# Brake_rev01.net
KiCad netlist of a schematic drawn in EAGLE
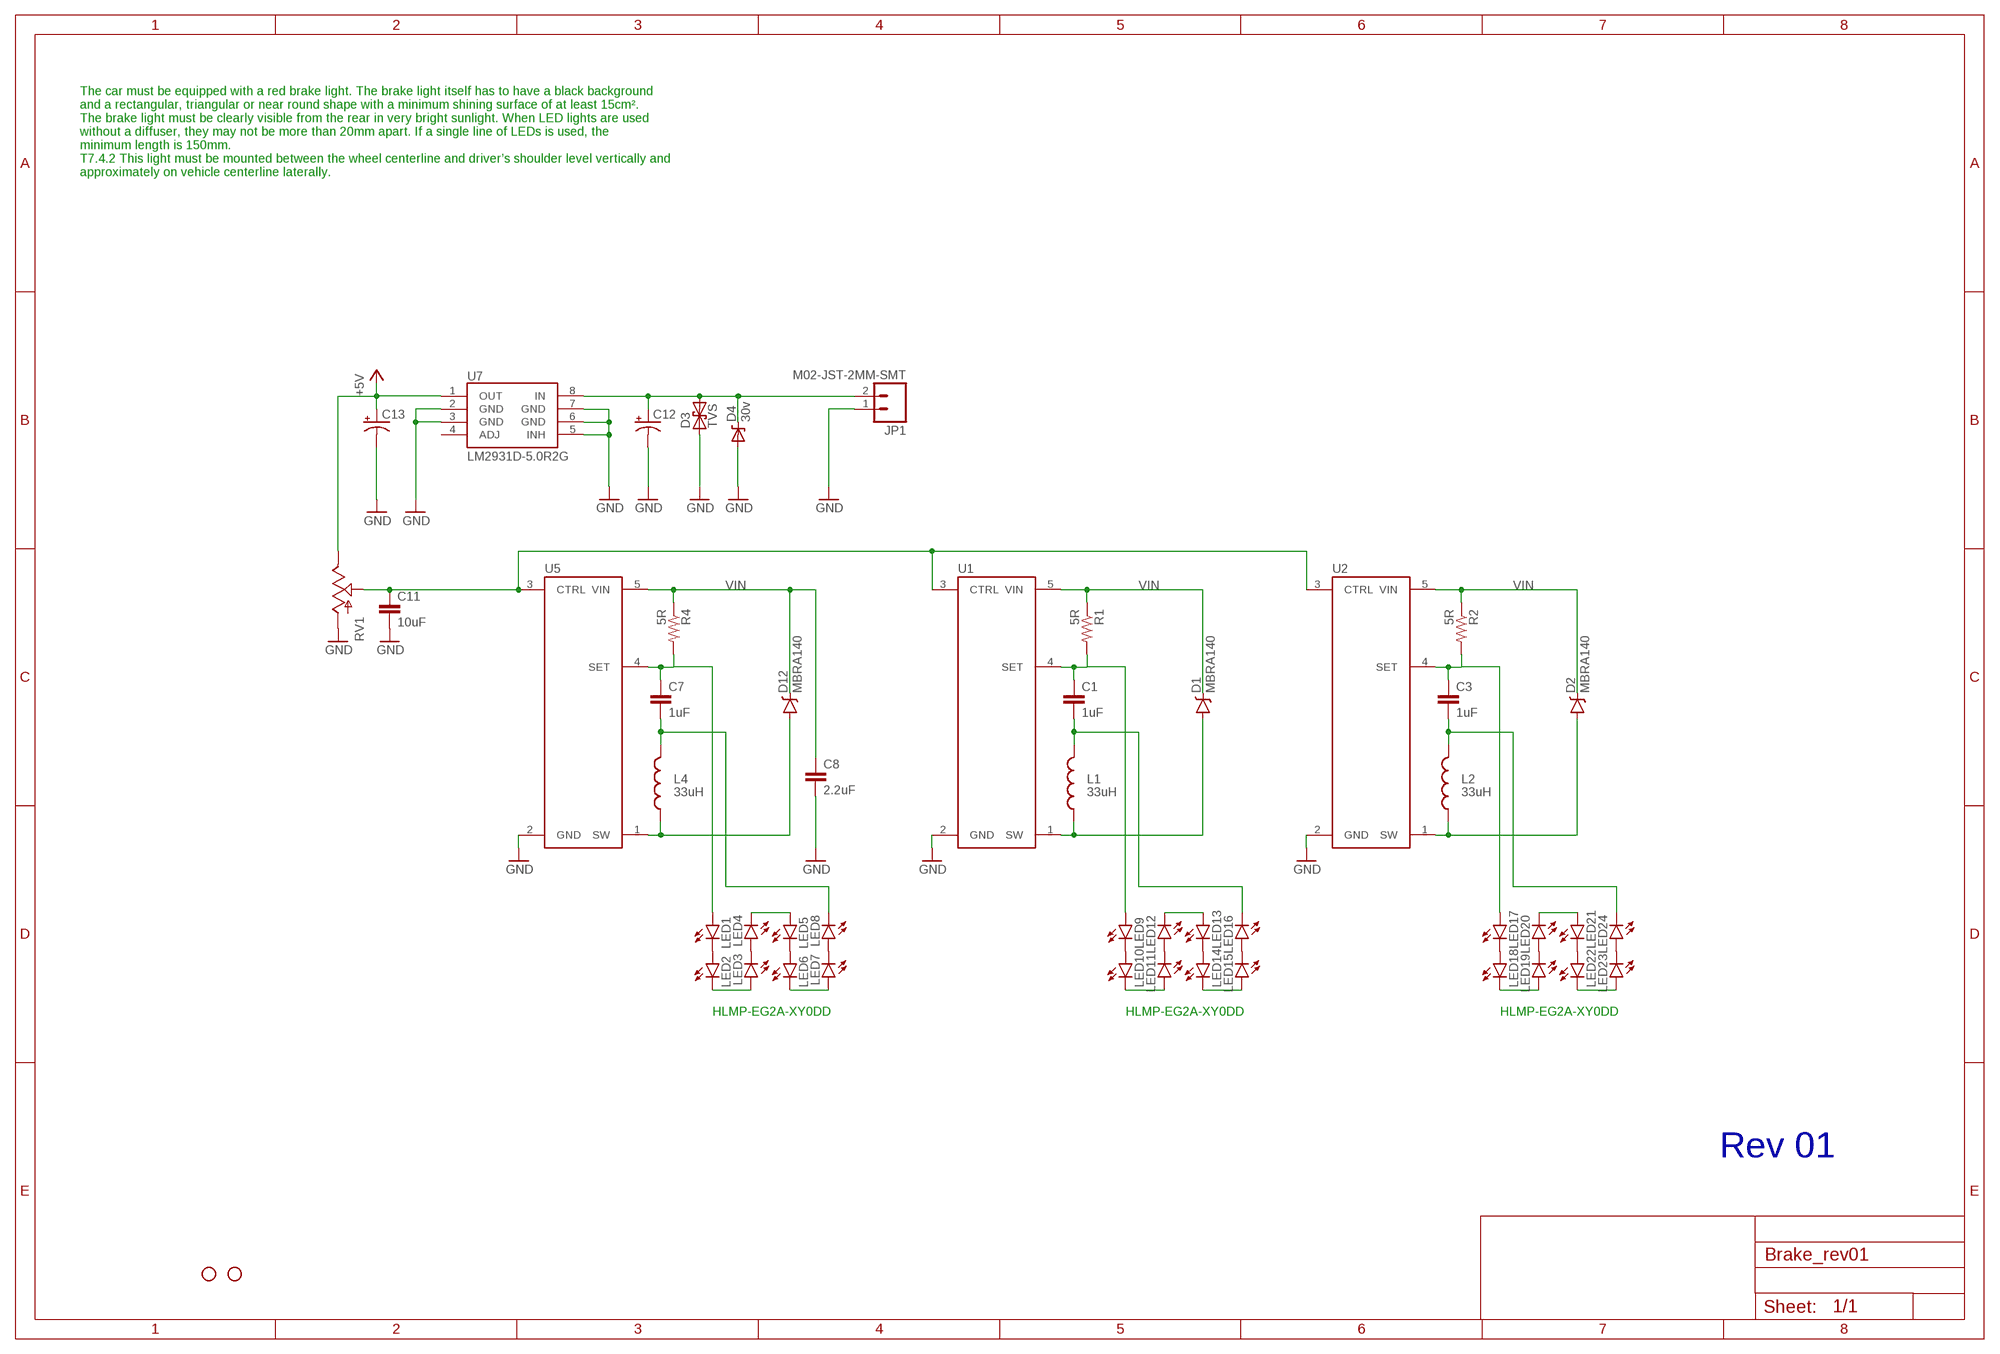
[diagram p0: schematic, sheet 1]

(export (version "E")
  (design (tool "Eeschema 10.0.6"))
  (components
    (comp (ref "C1")
      (value "1uF")
      (footprint "eagle-import:1206")
      (libsource (lib "eagle-import") (part "1.0UF50V10%(1206)"))
    )
    (comp (ref "C3")
      (value "1uF")
      (footprint "eagle-import:1206")
      (libsource (lib "eagle-import") (part "1.0UF50V10%(1206)"))
    )
    (comp (ref "C7")
      (value "1uF")
      (footprint "eagle-import:1206")
      (libsource (lib "eagle-import") (part "1.0UF50V10%(1206)"))
    )
    (comp (ref "C8")
      (value "2.2uF")
      (footprint "eagle-import:1206")
      (libsource (lib "eagle-import") (part "2.2UF50V10%(1206)"))
    )
    (comp (ref "C11")
      (value "10uF")
      (footprint "eagle-import:0805")
      (libsource (lib "eagle-import") (part "CAP0805"))
    )
    (comp (ref "C12")
      (value "CAP_POL6032")
      (footprint "eagle-import:EIA6032")
      (libsource (lib "eagle-import") (part "CAP_POL6032"))
    )
    (comp (ref "C13")
      (value "CAP_POL1206")
      (footprint "eagle-import:EIA3216")
      (libsource (lib "eagle-import") (part "CAP_POL1206"))
    )
    (comp (ref "D1")
      (value "MBRA140")
      (footprint "eagle-import:SMA-DIODE")
      (libsource (lib "eagle-import") (part "DIODE-SCHOTTKY-MBRA140"))
    )
    (comp (ref "D2")
      (value "MBRA140")
      (footprint "eagle-import:SMA-DIODE")
      (libsource (lib "eagle-import") (part "DIODE-SCHOTTKY-MBRA140"))
    )
    (comp (ref "D3")
      (value "TVS")
      (footprint "eagle-import:SMA-DIODE")
      (libsource (lib "eagle-import") (part "TVS"))
    )
    (comp (ref "D4")
      (value "30v")
      (footprint "eagle-import:SMB-DIODE")
      (libsource (lib "eagle-import") (part "DIODE-ZENERSMB"))
    )
    (comp (ref "D12")
      (value "MBRA140")
      (footprint "eagle-import:SMA-DIODE")
      (libsource (lib "eagle-import") (part "DIODE-SCHOTTKY-MBRA140"))
    )
    (comp (ref "JP1")
      (value "M02-JST-2MM-SMT")
      (footprint "eagle-import:JST-2-SMD")
      (libsource (lib "eagle-import") (part "M02-JST-2MM-SMT"))
    )
    (comp (ref "L1")
      (value "33uH")
      (footprint "eagle-import:SRN6045")
      (libsource (lib "eagle-import") (part "INDUCTORBOURNS_SRN6045"))
    )
    (comp (ref "L2")
      (value "33uH")
      (footprint "eagle-import:SRN6045")
      (libsource (lib "eagle-import") (part "INDUCTORBOURNS_SRN6045"))
    )
    (comp (ref "L4")
      (value "33uH")
      (footprint "eagle-import:SRN6045")
      (libsource (lib "eagle-import") (part "INDUCTORBOURNS_SRN6045"))
    )
    (comp (ref "LED1")
      (value "LED5MM")
      (footprint "eagle-import:LED5MM")
      (libsource (lib "eagle-import") (part "LED5MM"))
    )
    (comp (ref "LED2")
      (value "LED5MM")
      (footprint "eagle-import:LED5MM")
      (libsource (lib "eagle-import") (part "LED5MM"))
    )
    (comp (ref "LED3")
      (value "LED5MM")
      (footprint "eagle-import:LED5MM")
      (libsource (lib "eagle-import") (part "LED5MM"))
    )
    (comp (ref "LED4")
      (value "LED5MM")
      (footprint "eagle-import:LED5MM")
      (libsource (lib "eagle-import") (part "LED5MM"))
    )
    (comp (ref "LED5")
      (value "LED5MM")
      (footprint "eagle-import:LED5MM")
      (libsource (lib "eagle-import") (part "LED5MM"))
    )
    (comp (ref "LED6")
      (value "LED5MM")
      (footprint "eagle-import:LED5MM")
      (libsource (lib "eagle-import") (part "LED5MM"))
    )
    (comp (ref "LED7")
      (value "LED5MM")
      (footprint "eagle-import:LED5MM")
      (libsource (lib "eagle-import") (part "LED5MM"))
    )
    (comp (ref "LED8")
      (value "LED5MM")
      (footprint "eagle-import:LED5MM")
      (libsource (lib "eagle-import") (part "LED5MM"))
    )
    (comp (ref "LED9")
      (value "LED5MM")
      (footprint "eagle-import:LED5MM")
      (libsource (lib "eagle-import") (part "LED5MM"))
    )
    (comp (ref "LED10")
      (value "LED5MM")
      (footprint "eagle-import:LED5MM")
      (libsource (lib "eagle-import") (part "LED5MM"))
    )
    (comp (ref "LED11")
      (value "LED5MM")
      (footprint "eagle-import:LED5MM")
      (libsource (lib "eagle-import") (part "LED5MM"))
    )
    (comp (ref "LED12")
      (value "LED5MM")
      (footprint "eagle-import:LED5MM")
      (libsource (lib "eagle-import") (part "LED5MM"))
    )
    (comp (ref "LED13")
      (value "LED5MM")
      (footprint "eagle-import:LED5MM")
      (libsource (lib "eagle-import") (part "LED5MM"))
    )
    (comp (ref "LED14")
      (value "LED5MM")
      (footprint "eagle-import:LED5MM")
      (libsource (lib "eagle-import") (part "LED5MM"))
    )
    (comp (ref "LED15")
      (value "LED5MM")
      (footprint "eagle-import:LED5MM")
      (libsource (lib "eagle-import") (part "LED5MM"))
    )
    (comp (ref "LED16")
      (value "LED5MM")
      (footprint "eagle-import:LED5MM")
      (libsource (lib "eagle-import") (part "LED5MM"))
    )
    (comp (ref "LED17")
      (value "LED5MM")
      (footprint "eagle-import:LED5MM")
      (libsource (lib "eagle-import") (part "LED5MM"))
    )
    (comp (ref "LED18")
      (value "LED5MM")
      (footprint "eagle-import:LED5MM")
      (libsource (lib "eagle-import") (part "LED5MM"))
    )
    (comp (ref "LED19")
      (value "LED5MM")
      (footprint "eagle-import:LED5MM")
      (libsource (lib "eagle-import") (part "LED5MM"))
    )
    (comp (ref "LED20")
      (value "LED5MM")
      (footprint "eagle-import:LED5MM")
      (libsource (lib "eagle-import") (part "LED5MM"))
    )
    (comp (ref "LED21")
      (value "LED5MM")
      (footprint "eagle-import:LED5MM")
      (libsource (lib "eagle-import") (part "LED5MM"))
    )
    (comp (ref "LED22")
      (value "LED5MM")
      (footprint "eagle-import:LED5MM")
      (libsource (lib "eagle-import") (part "LED5MM"))
    )
    (comp (ref "LED23")
      (value "LED5MM")
      (footprint "eagle-import:LED5MM")
      (libsource (lib "eagle-import") (part "LED5MM"))
    )
    (comp (ref "LED24")
      (value "LED5MM")
      (footprint "eagle-import:LED5MM")
      (libsource (lib "eagle-import") (part "LED5MM"))
    )
    (comp (ref "R1")
      (value "5R")
      (footprint "eagle-import:0805")
      (libsource (lib "eagle-import") (part "0.3OHM-1/8W-1%(0805)"))
    )
    (comp (ref "R2")
      (value "5R")
      (footprint "eagle-import:0805")
      (libsource (lib "eagle-import") (part "0.3OHM-1/8W-1%(0805)"))
    )
    (comp (ref "R4")
      (value "5R")
      (footprint "eagle-import:0805")
      (libsource (lib "eagle-import") (part "0.3OHM-1/8W-1%(0805)"))
    )
    (comp (ref "RV1")
      (value "POTTRIM")
      (footprint "eagle-import:TRIM_POT")
      (libsource (lib "eagle-import") (part "POTTRIM"))
    )
    (comp (ref "STANDOFF1")
      (value "STAND-OFF")
      (footprint "eagle-import:STAND-OFF")
      (libsource (lib "eagle-import") (part "STAND-OFF"))
    )
    (comp (ref "STANDOFF2")
      (value "STAND-OFF")
      (footprint "eagle-import:STAND-OFF")
      (libsource (lib "eagle-import") (part "STAND-OFF"))
    )
    (comp (ref "U1")
      (value "AL8805")
      (footprint "eagle-import:SOT23-5")
      (libsource (lib "eagle-import") (part "AL8805"))
    )
    (comp (ref "U2")
      (value "AL8805")
      (footprint "eagle-import:SOT23-5")
      (libsource (lib "eagle-import") (part "AL8805"))
    )
    (comp (ref "U5")
      (value "AL8805")
      (footprint "eagle-import:SOT23-5")
      (libsource (lib "eagle-import") (part "AL8805"))
    )
    (comp (ref "U7")
      (value "LM2931D-5.0R2G")
      (footprint "eagle-import:SO08")
      (libsource (lib "eagle-import") (part "LM2931"))
    )
  )
  (nets
    (net (code "1") (name "+5V") (class "Default")
      (node (ref "C13") (pin "A") (pinfunction "+_A") (pintype "passive"))
      (node (ref "RV1") (pin "2") (pinfunction "E_2") (pintype "passive"))
      (node (ref "U7") (pin "1") (pinfunction "OUT_1") (pintype "bidirectional"))
    )
    (net (code "2") (name "/VIN") (class "Default")
      (node (ref "C12") (pin "P$1") (pinfunction "+_P$1") (pintype "passive"))
      (node (ref "C8") (pin "1") (pinfunction "1_1") (pintype "passive"))
      (node (ref "D1") (pin "C") (pinfunction "C_C") (pintype "passive"))
      (node (ref "D12") (pin "C") (pinfunction "C_C") (pintype "passive"))
      (node (ref "D2") (pin "C") (pinfunction "C_C") (pintype "passive"))
      (node (ref "D3") (pin "C") (pinfunction "2_C") (pintype "passive"))
      (node (ref "D4") (pin "C") (pinfunction "C_C") (pintype "passive"))
      (node (ref "JP1") (pin "2") (pinfunction "1_2") (pintype "passive"))
      (node (ref "R1") (pin "1") (pinfunction "1_1") (pintype "passive"))
      (node (ref "R2") (pin "1") (pinfunction "1_1") (pintype "passive"))
      (node (ref "R4") (pin "1") (pinfunction "1_1") (pintype "passive"))
      (node (ref "U1") (pin "5") (pinfunction "VIN_5") (pintype "bidirectional"))
      (node (ref "U2") (pin "5") (pinfunction "VIN_5") (pintype "bidirectional"))
      (node (ref "U5") (pin "5") (pinfunction "VIN_5") (pintype "bidirectional"))
      (node (ref "U7") (pin "8") (pinfunction "IN_8") (pintype "bidirectional"))
    )
    (net (code "3") (name "GND") (class "Default")
      (node (ref "C11") (pin "2") (pinfunction "2_2") (pintype "passive"))
      (node (ref "C12") (pin "P$2") (pinfunction "-_P$2") (pintype "passive"))
      (node (ref "C13") (pin "C") (pinfunction "-_C") (pintype "passive"))
      (node (ref "C8") (pin "2") (pinfunction "2_2") (pintype "passive"))
      (node (ref "D3") (pin "A") (pinfunction "1_A") (pintype "passive"))
      (node (ref "D4") (pin "A") (pinfunction "A_A") (pintype "passive"))
      (node (ref "JP1") (pin "1") (pinfunction "2_1") (pintype "passive"))
      (node (ref "RV1") (pin "3") (pinfunction "A_3") (pintype "passive"))
      (node (ref "U1") (pin "2") (pinfunction "GND_2") (pintype "bidirectional"))
      (node (ref "U2") (pin "2") (pinfunction "GND_2") (pintype "bidirectional"))
      (node (ref "U5") (pin "2") (pinfunction "GND_2") (pintype "bidirectional"))
      (node (ref "U7") (pin "2") (pinfunction "GND_2") (pintype "bidirectional"))
      (node (ref "U7") (pin "3") (pinfunction "GND_3") (pintype "bidirectional"))
      (node (ref "U7") (pin "5") (pinfunction "INH_5") (pintype "bidirectional"))
      (node (ref "U7") (pin "6") (pinfunction "GND_6") (pintype "bidirectional"))
      (node (ref "U7") (pin "7") (pinfunction "GND_7") (pintype "bidirectional"))
    )
    (net (code "4") (name "Net-(LED1-C)") (class "Default")
      (node (ref "LED1") (pin "K") (pinfunction "C_K") (pintype "passive"))
      (node (ref "LED2") (pin "A") (pinfunction "A_A") (pintype "passive"))
    )
    (net (code "5") (name "Net-(LED2-C)") (class "Default")
      (node (ref "LED2") (pin "K") (pinfunction "C_K") (pintype "passive"))
      (node (ref "LED3") (pin "A") (pinfunction "A_A") (pintype "passive"))
    )
    (net (code "6") (name "Net-(LED3-C)") (class "Default")
      (node (ref "LED3") (pin "K") (pinfunction "C_K") (pintype "passive"))
      (node (ref "LED4") (pin "A") (pinfunction "A_A") (pintype "passive"))
    )
    (net (code "7") (name "Net-(LED4-C)") (class "Default")
      (node (ref "LED4") (pin "K") (pinfunction "C_K") (pintype "passive"))
      (node (ref "LED5") (pin "A") (pinfunction "A_A") (pintype "passive"))
    )
    (net (code "8") (name "Net-(LED5-C)") (class "Default")
      (node (ref "LED5") (pin "K") (pinfunction "C_K") (pintype "passive"))
      (node (ref "LED6") (pin "A") (pinfunction "A_A") (pintype "passive"))
    )
    (net (code "9") (name "Net-(LED6-C)") (class "Default")
      (node (ref "LED6") (pin "K") (pinfunction "C_K") (pintype "passive"))
      (node (ref "LED7") (pin "A") (pinfunction "A_A") (pintype "passive"))
    )
    (net (code "10") (name "Net-(LED7-C)") (class "Default")
      (node (ref "LED7") (pin "K") (pinfunction "C_K") (pintype "passive"))
      (node (ref "LED8") (pin "A") (pinfunction "A_A") (pintype "passive"))
    )
    (net (code "11") (name "Net-(LED8-C)") (class "Default")
      (node (ref "C7") (pin "2") (pinfunction "2_2") (pintype "passive"))
      (node (ref "L4") (pin "2") (pinfunction "2_2") (pintype "passive"))
      (node (ref "LED8") (pin "K") (pinfunction "C_K") (pintype "passive"))
    )
    (net (code "12") (name "Net-(LED9-C)") (class "Default")
      (node (ref "LED10") (pin "A") (pinfunction "A_A") (pintype "passive"))
      (node (ref "LED9") (pin "K") (pinfunction "C_K") (pintype "passive"))
    )
    (net (code "13") (name "Net-(LED10-C)") (class "Default")
      (node (ref "LED10") (pin "K") (pinfunction "C_K") (pintype "passive"))
      (node (ref "LED11") (pin "A") (pinfunction "A_A") (pintype "passive"))
    )
    (net (code "14") (name "Net-(LED11-C)") (class "Default")
      (node (ref "LED11") (pin "K") (pinfunction "C_K") (pintype "passive"))
      (node (ref "LED12") (pin "A") (pinfunction "A_A") (pintype "passive"))
    )
    (net (code "15") (name "Net-(LED12-C)") (class "Default")
      (node (ref "LED12") (pin "K") (pinfunction "C_K") (pintype "passive"))
      (node (ref "LED13") (pin "A") (pinfunction "A_A") (pintype "passive"))
    )
    (net (code "16") (name "Net-(LED13-C)") (class "Default")
      (node (ref "LED13") (pin "K") (pinfunction "C_K") (pintype "passive"))
      (node (ref "LED14") (pin "A") (pinfunction "A_A") (pintype "passive"))
    )
    (net (code "17") (name "Net-(LED14-C)") (class "Default")
      (node (ref "LED14") (pin "K") (pinfunction "C_K") (pintype "passive"))
      (node (ref "LED15") (pin "A") (pinfunction "A_A") (pintype "passive"))
    )
    (net (code "18") (name "Net-(LED15-C)") (class "Default")
      (node (ref "LED15") (pin "K") (pinfunction "C_K") (pintype "passive"))
      (node (ref "LED16") (pin "A") (pinfunction "A_A") (pintype "passive"))
    )
    (net (code "19") (name "Net-(LED16-C)") (class "Default")
      (node (ref "C1") (pin "2") (pinfunction "2_2") (pintype "passive"))
      (node (ref "L1") (pin "2") (pinfunction "2_2") (pintype "passive"))
      (node (ref "LED16") (pin "K") (pinfunction "C_K") (pintype "passive"))
    )
    (net (code "20") (name "Net-(LED17-C)") (class "Default")
      (node (ref "LED17") (pin "K") (pinfunction "C_K") (pintype "passive"))
      (node (ref "LED18") (pin "A") (pinfunction "A_A") (pintype "passive"))
    )
    (net (code "21") (name "Net-(LED18-C)") (class "Default")
      (node (ref "LED18") (pin "K") (pinfunction "C_K") (pintype "passive"))
      (node (ref "LED19") (pin "A") (pinfunction "A_A") (pintype "passive"))
    )
    (net (code "22") (name "Net-(LED19-C)") (class "Default")
      (node (ref "LED19") (pin "K") (pinfunction "C_K") (pintype "passive"))
      (node (ref "LED20") (pin "A") (pinfunction "A_A") (pintype "passive"))
    )
    (net (code "23") (name "Net-(LED20-C)") (class "Default")
      (node (ref "LED20") (pin "K") (pinfunction "C_K") (pintype "passive"))
      (node (ref "LED21") (pin "A") (pinfunction "A_A") (pintype "passive"))
    )
    (net (code "24") (name "Net-(LED21-C)") (class "Default")
      (node (ref "LED21") (pin "K") (pinfunction "C_K") (pintype "passive"))
      (node (ref "LED22") (pin "A") (pinfunction "A_A") (pintype "passive"))
    )
    (net (code "25") (name "Net-(LED22-C)") (class "Default")
      (node (ref "LED22") (pin "K") (pinfunction "C_K") (pintype "passive"))
      (node (ref "LED23") (pin "A") (pinfunction "A_A") (pintype "passive"))
    )
    (net (code "26") (name "Net-(LED23-C)") (class "Default")
      (node (ref "LED23") (pin "K") (pinfunction "C_K") (pintype "passive"))
      (node (ref "LED24") (pin "A") (pinfunction "A_A") (pintype "passive"))
    )
    (net (code "27") (name "Net-(LED24-C)") (class "Default")
      (node (ref "C3") (pin "2") (pinfunction "2_2") (pintype "passive"))
      (node (ref "L2") (pin "2") (pinfunction "2_2") (pintype "passive"))
      (node (ref "LED24") (pin "K") (pinfunction "C_K") (pintype "passive"))
    )
    (net (code "28") (name "Net-(RV1-S)") (class "Default")
      (node (ref "C11") (pin "1") (pinfunction "1_1") (pintype "passive"))
      (node (ref "RV1") (pin "1") (pinfunction "S_1") (pintype "passive"))
      (node (ref "U1") (pin "3") (pinfunction "CTRL_3") (pintype "bidirectional"))
      (node (ref "U2") (pin "3") (pinfunction "CTRL_3") (pintype "bidirectional"))
      (node (ref "U5") (pin "3") (pinfunction "CTRL_3") (pintype "bidirectional"))
    )
    (net (code "29") (name "Net-(U1-SET)") (class "Default")
      (node (ref "C1") (pin "1") (pinfunction "1_1") (pintype "passive"))
      (node (ref "LED9") (pin "A") (pinfunction "A_A") (pintype "passive"))
      (node (ref "R1") (pin "2") (pinfunction "2_2") (pintype "passive"))
      (node (ref "U1") (pin "4") (pinfunction "SET_4") (pintype "bidirectional"))
    )
    (net (code "30") (name "Net-(U1-SW)") (class "Default")
      (node (ref "D1") (pin "A") (pinfunction "A_A") (pintype "passive"))
      (node (ref "L1") (pin "1") (pinfunction "1_1") (pintype "passive"))
      (node (ref "U1") (pin "1") (pinfunction "SW_1") (pintype "bidirectional"))
    )
    (net (code "31") (name "Net-(U2-SET)") (class "Default")
      (node (ref "C3") (pin "1") (pinfunction "1_1") (pintype "passive"))
      (node (ref "LED17") (pin "A") (pinfunction "A_A") (pintype "passive"))
      (node (ref "R2") (pin "2") (pinfunction "2_2") (pintype "passive"))
      (node (ref "U2") (pin "4") (pinfunction "SET_4") (pintype "bidirectional"))
    )
    (net (code "32") (name "Net-(U2-SW)") (class "Default")
      (node (ref "D2") (pin "A") (pinfunction "A_A") (pintype "passive"))
      (node (ref "L2") (pin "1") (pinfunction "1_1") (pintype "passive"))
      (node (ref "U2") (pin "1") (pinfunction "SW_1") (pintype "bidirectional"))
    )
    (net (code "33") (name "Net-(U5-SET)") (class "Default")
      (node (ref "C7") (pin "1") (pinfunction "1_1") (pintype "passive"))
      (node (ref "LED1") (pin "A") (pinfunction "A_A") (pintype "passive"))
      (node (ref "R4") (pin "2") (pinfunction "2_2") (pintype "passive"))
      (node (ref "U5") (pin "4") (pinfunction "SET_4") (pintype "bidirectional"))
    )
    (net (code "34") (name "Net-(U5-SW)") (class "Default")
      (node (ref "D12") (pin "A") (pinfunction "A_A") (pintype "passive"))
      (node (ref "L4") (pin "1") (pinfunction "1_1") (pintype "passive"))
      (node (ref "U5") (pin "1") (pinfunction "SW_1") (pintype "bidirectional"))
    )
    (net (code "35") (name "unconnected-(U7-ADJ-Pad4)") (class "Default")
      (node (ref "U7") (pin "4") (pinfunction "ADJ_4") (pintype "bidirectional"))
    )
  )
)
